# pcb_control_esp.net
KiCad netlist of a schematic drawn in EAGLE
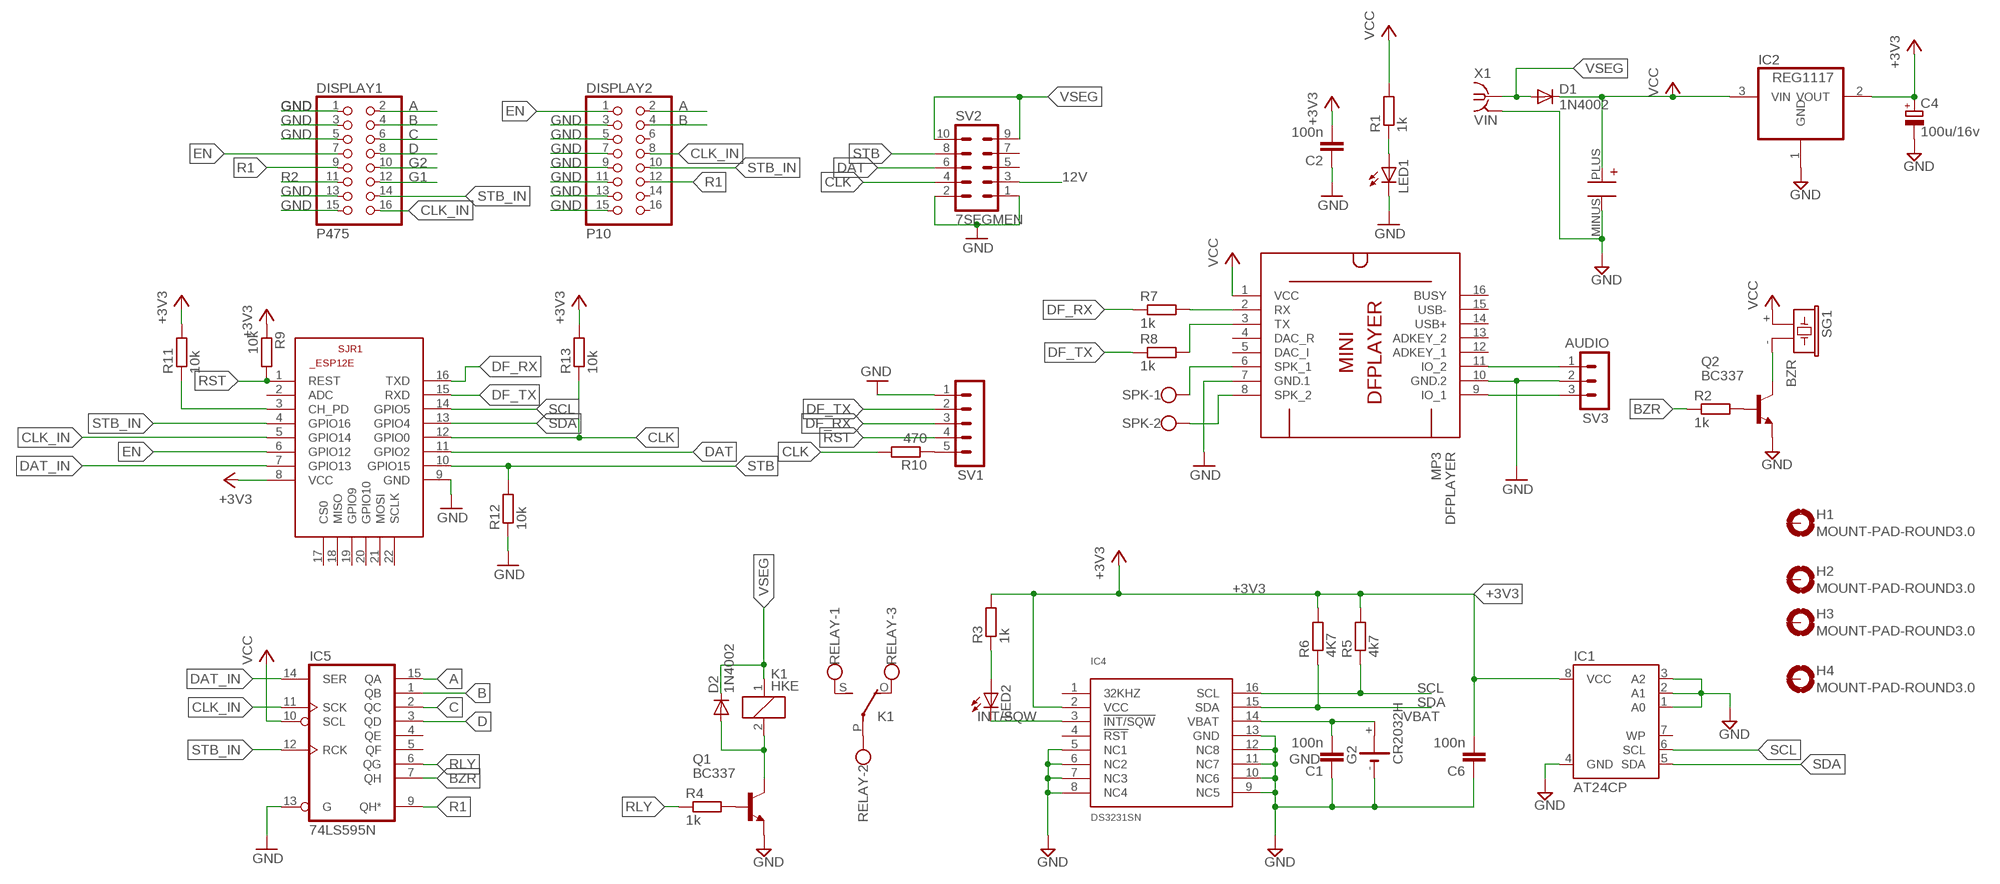
[diagram p0: schematic, sheet 1]

(export (version "E")
  (design (tool "Eeschema 10.0.6"))
  (components
    (comp (ref "C1")
      (value "100n")
      (footprint "eagle-import:C025-024X044")
      (libsource (lib "eagle-import") (part "C-EU025-024X044"))
    )
    (comp (ref "C2")
      (value "100n")
      (footprint "eagle-import:C025-024X044")
      (libsource (lib "eagle-import") (part "C-EU025-024X044"))
    )
    (comp (ref "C4")
      (value "100u/16v")
      (footprint "eagle-import:E2,5-5")
      (libsource (lib "eagle-import") (part "CPOL-EUE2.5-5"))
    )
    (comp (ref "C6")
      (value "100n")
      (footprint "eagle-import:C025-024X044")
      (libsource (lib "eagle-import") (part "C-EU025-024X044"))
    )
    (comp (ref "C24")
      (value "1000U")
      (footprint "eagle-import:EEU-FR1C471B")
      (libsource (lib "eagle-import") (part "EEU-FR1C471B"))
    )
    (comp (ref "D1")
      (value "1N4002")
      (footprint "eagle-import:DO35-10")
      (libsource (lib "eagle-import") (part "1N4148DO35-10"))
    )
    (comp (ref "D2")
      (value "1N4002")
      (footprint "eagle-import:DO35-10")
      (libsource (lib "eagle-import") (part "1N4148DO35-10"))
    )
    (comp (ref "DFPLAYER")
      (value "MP3")
      (footprint "eagle-import:DFPLAYER-MINI-MODULE")
      (libsource (lib "eagle-import") (part "DFPLAYER-MINI-MODULE"))
    )
    (comp (ref "DISPLAY1")
      (value "P475")
      (footprint "eagle-import:2X08")
      (libsource (lib "eagle-import") (part "PINHD-2X8"))
    )
    (comp (ref "DISPLAY2")
      (value "P10")
      (footprint "eagle-import:2X08")
      (libsource (lib "eagle-import") (part "PINHD-2X8"))
    )
    (comp (ref "G2")
      (value "CR2032H")
      (footprint "eagle-import:CR2032H")
      (libsource (lib "eagle-import") (part "CR2032H"))
    )
    (comp (ref "H1")
      (value "MOUNT-PAD-ROUND3.0")
      (footprint "eagle-import:3,0-PAD")
      (libsource (lib "eagle-import") (part "MOUNT-PAD-ROUND3.0"))
    )
    (comp (ref "H2")
      (value "MOUNT-PAD-ROUND3.0")
      (footprint "eagle-import:3,0-PAD")
      (libsource (lib "eagle-import") (part "MOUNT-PAD-ROUND3.0"))
    )
    (comp (ref "H3")
      (value "MOUNT-PAD-ROUND3.0")
      (footprint "eagle-import:3,0-PAD")
      (libsource (lib "eagle-import") (part "MOUNT-PAD-ROUND3.0"))
    )
    (comp (ref "H4")
      (value "MOUNT-PAD-ROUND3.0")
      (footprint "eagle-import:3,0-PAD")
      (libsource (lib "eagle-import") (part "MOUNT-PAD-ROUND3.0"))
    )
    (comp (ref "IC1")
      (value "AT24CP")
      (footprint "eagle-import:DIL08")
      (fields (field (name "MPN") "AT24C1024BW-SH-B"))
      (libsource (lib "eagle-import") (part "AT24CP"))
    )
    (comp (ref "IC2")
      (value "REG1117")
      (footprint "eagle-import:SOT223")
      (libsource (lib "eagle-import") (part "REG1117"))
    )
    (comp (ref "IC4")
      (value "DS3231SN")
      (footprint "eagle-import:SO16W")
      (libsource (lib "eagle-import") (part "DS3231SN"))
    )
    (comp (ref "IC5")
      (value "74LS595N")
      (footprint "eagle-import:DIL16")
      (libsource (lib "eagle-import") (part "74595NLS"))
    )
    (comp (ref "K1")
      (value "HKE")
      (footprint "eagle-import:ZF112")
      (libsource (lib "eagle-import") (part "ZF112"))
    )
    (comp (ref "LED1")
      (value "LED3MM")
      (footprint "eagle-import:LED3MM")
      (libsource (lib "eagle-import") (part "LED3MM"))
    )
    (comp (ref "LED2")
      (value "LED3MM")
      (footprint "eagle-import:LED3MM")
      (libsource (lib "eagle-import") (part "LED3MM"))
    )
    (comp (ref "Q1")
      (value "BC337")
      (footprint "eagle-import:TO92-EBC")
      (libsource (lib "eagle-import") (part "BC548"))
    )
    (comp (ref "Q2")
      (value "BC337")
      (footprint "eagle-import:TO92-EBC")
      (libsource (lib "eagle-import") (part "BC548"))
    )
    (comp (ref "R1")
      (value "1k")
      (footprint "eagle-import:0207_7")
      (libsource (lib "eagle-import") (part "R-EU_0207/7"))
    )
    (comp (ref "R2")
      (value "1k")
      (footprint "eagle-import:0207_7")
      (libsource (lib "eagle-import") (part "R-EU_0207/7"))
    )
    (comp (ref "R3")
      (value "1k")
      (footprint "eagle-import:0207_7")
      (libsource (lib "eagle-import") (part "R-EU_0207/7"))
    )
    (comp (ref "R4")
      (value "1k")
      (footprint "eagle-import:0207_7")
      (libsource (lib "eagle-import") (part "R-EU_0207/7"))
    )
    (comp (ref "R5")
      (value "4k7")
      (footprint "eagle-import:0207_7")
      (libsource (lib "eagle-import") (part "R-EU_0207/7"))
    )
    (comp (ref "R6")
      (value "4K7")
      (footprint "eagle-import:0207_7")
      (libsource (lib "eagle-import") (part "R-EU_0207/7"))
    )
    (comp (ref "R7")
      (value "1k")
      (footprint "eagle-import:0207_7")
      (libsource (lib "eagle-import") (part "R-EU_0207/7"))
    )
    (comp (ref "R8")
      (value "1k")
      (footprint "eagle-import:0207_7")
      (libsource (lib "eagle-import") (part "R-EU_0207/7"))
    )
    (comp (ref "R9")
      (value "10k")
      (footprint "eagle-import:0207_7")
      (libsource (lib "eagle-import") (part "R-EU_0207/7"))
    )
    (comp (ref "R10")
      (value "470")
      (footprint "eagle-import:0207_7")
      (libsource (lib "eagle-import") (part "R-EU_0207/7"))
    )
    (comp (ref "R11")
      (value "10k")
      (footprint "eagle-import:0207_7")
      (libsource (lib "eagle-import") (part "R-EU_0207/7"))
    )
    (comp (ref "R12")
      (value "10k")
      (footprint "eagle-import:0207_7")
      (libsource (lib "eagle-import") (part "R-EU_0207/7"))
    )
    (comp (ref "R13")
      (value "10k")
      (footprint "eagle-import:0207_7")
      (libsource (lib "eagle-import") (part "R-EU_0207/7"))
    )
    (comp (ref "RELAY")
      (value "W237-103")
      (footprint "eagle-import:W237-103")
      (fields (field (name "MPN") "237-103"))
      (libsource (lib "eagle-import") (part "W237-103"))
    )
    (comp (ref "SG1")
      (value "BZR")
      (footprint "eagle-import:F_CM12P")
      (libsource (lib "eagle-import") (part "F/CM12P"))
    )
    (comp (ref "SJR1")
      (value "ESP8266-12EESP12E")
      (footprint "eagle-import:ESP8266-ESP12E")
      (libsource (lib "eagle-import") (part "ESP8266-12EESP12E"))
    )
    (comp (ref "SPK")
      (value "W237-102")
      (footprint "eagle-import:W237-102")
      (fields (field (name "MPN") "237-102"))
      (libsource (lib "eagle-import") (part "W237-102"))
    )
    (comp (ref "SV1")
      (value "MA05-1")
      (footprint "eagle-import:MA05-1")
      (libsource (lib "eagle-import") (part "MA05-1"))
    )
    (comp (ref "SV2")
      (value "7SEGMEN")
      (footprint "eagle-import:MA05-2")
      (libsource (lib "eagle-import") (part "MA05-2"))
    )
    (comp (ref "SV3")
      (value "AUDIO")
      (footprint "eagle-import:MA03-1")
      (libsource (lib "eagle-import") (part "MA03-1"))
    )
    (comp (ref "X1")
      (value "VIN")
      (footprint "eagle-import:J502-ND")
      (libsource (lib "eagle-import") (part "SMA-J502-ND"))
    )
  )
  (nets
    (net (code "1") (name "+3V3") (class "Default")
      (node (ref "C2") (pin "2") (pinfunction "2_2") (pintype "passive"))
      (node (ref "C4") (pin "+") (pinfunction "+_+") (pintype "passive"))
      (node (ref "C6") (pin "2") (pinfunction "2_2") (pintype "passive"))
      (node (ref "IC1") (pin "8") (pinfunction "VCC_8") (pintype "power_in"))
      (node (ref "IC2") (pin "2") (pinfunction "VOUT_2") (pintype "output"))
      (node (ref "IC4") (pin "2") (pinfunction "VCC_2") (pintype "bidirectional"))
      (node (ref "R11") (pin "2") (pinfunction "2_2") (pintype "passive"))
      (node (ref "R13") (pin "2") (pinfunction "2_2") (pintype "passive"))
      (node (ref "R3") (pin "2") (pinfunction "2_2") (pintype "passive"))
      (node (ref "R5") (pin "2") (pinfunction "2_2") (pintype "passive"))
      (node (ref "R6") (pin "2") (pinfunction "2_2") (pintype "passive"))
      (node (ref "R9") (pin "1") (pinfunction "1_1") (pintype "passive"))
      (node (ref "SJR1") (pin "8") (pinfunction "VCC_8") (pintype "bidirectional"))
    )
    (net (code "2") (name "/12V") (class "Default")
      (node (ref "SV2") (pin "3") (pinfunction "3_3") (pintype "passive"))
    )
    (net (code "3") (name "/G1") (class "Default")
      (node (ref "DISPLAY1") (pin "12") (pinfunction "12_12") (pintype "passive"))
    )
    (net (code "4") (name "/G2") (class "Default")
      (node (ref "DISPLAY1") (pin "10") (pinfunction "10_10") (pintype "passive"))
    )
    (net (code "5") (name "/INT{slash}SQW") (class "Default")
      (node (ref "IC4") (pin "3") (pinfunction "~{INT/SQW}_3") (pintype "bidirectional"))
      (node (ref "LED2") (pin "K") (pinfunction "C_K") (pintype "passive"))
    )
    (net (code "6") (name "/R2") (class "Default")
      (node (ref "DISPLAY1") (pin "11") (pinfunction "11_11") (pintype "passive"))
    )
    (net (code "7") (name "/VBAT") (class "Default")
      (node (ref "C1") (pin "2") (pinfunction "2_2") (pintype "passive"))
      (node (ref "G2") (pin "+") (pinfunction "+_+") (pintype "passive"))
      (node (ref "IC4") (pin "14") (pinfunction "VBAT_14") (pintype "bidirectional"))
    )
    (net (code "8") (name "A") (class "Default")
      (node (ref "DISPLAY1") (pin "2") (pinfunction "2_2") (pintype "passive"))
      (node (ref "DISPLAY2") (pin "2") (pinfunction "2_2") (pintype "passive"))
      (node (ref "IC5") (pin "15") (pinfunction "QA_15") (pintype "tri_state"))
    )
    (net (code "9") (name "B") (class "Default")
      (node (ref "DISPLAY1") (pin "4") (pinfunction "4_4") (pintype "passive"))
      (node (ref "DISPLAY2") (pin "4") (pinfunction "4_4") (pintype "passive"))
      (node (ref "IC5") (pin "1") (pinfunction "QB_1") (pintype "tri_state"))
    )
    (net (code "10") (name "BZR") (class "Default")
      (node (ref "IC5") (pin "7") (pinfunction "QH_7") (pintype "tri_state"))
      (node (ref "R2") (pin "1") (pinfunction "1_1") (pintype "passive"))
    )
    (net (code "11") (name "C") (class "Default")
      (node (ref "DISPLAY1") (pin "6") (pinfunction "6_6") (pintype "passive"))
      (node (ref "IC5") (pin "2") (pinfunction "QC_2") (pintype "tri_state"))
    )
    (net (code "12") (name "CLK") (class "Default")
      (node (ref "R10") (pin "2") (pinfunction "2_2") (pintype "passive"))
      (node (ref "R13") (pin "1") (pinfunction "1_1") (pintype "passive"))
      (node (ref "SJR1") (pin "12") (pinfunction "GPIO0_12") (pintype "bidirectional"))
      (node (ref "SV2") (pin "4") (pinfunction "4_4") (pintype "passive"))
    )
    (net (code "13") (name "CLK_IN") (class "Default")
      (node (ref "DISPLAY1") (pin "16") (pinfunction "16_16") (pintype "passive"))
      (node (ref "DISPLAY2") (pin "8") (pinfunction "8_8") (pintype "passive"))
      (node (ref "IC5") (pin "11") (pinfunction "SCK_11") (pintype "input"))
      (node (ref "SJR1") (pin "5") (pinfunction "GPIO14_5") (pintype "bidirectional"))
    )
    (net (code "14") (name "D") (class "Default")
      (node (ref "DISPLAY1") (pin "8") (pinfunction "8_8") (pintype "passive"))
      (node (ref "IC5") (pin "3") (pinfunction "QD_3") (pintype "tri_state"))
    )
    (net (code "15") (name "DAT") (class "Default")
      (node (ref "SJR1") (pin "11") (pinfunction "GPIO2_11") (pintype "bidirectional"))
      (node (ref "SV2") (pin "6") (pinfunction "6_6") (pintype "passive"))
    )
    (net (code "16") (name "DAT_IN") (class "Default")
      (node (ref "IC5") (pin "14") (pinfunction "SER_14") (pintype "input"))
      (node (ref "SJR1") (pin "7") (pinfunction "GPIO13_7") (pintype "bidirectional"))
    )
    (net (code "17") (name "DF_RX") (class "Default")
      (node (ref "R7") (pin "1") (pinfunction "1_1") (pintype "passive"))
      (node (ref "SJR1") (pin "16") (pinfunction "TXD_16") (pintype "bidirectional"))
      (node (ref "SV1") (pin "3") (pinfunction "3_3") (pintype "passive"))
    )
    (net (code "18") (name "DF_TX") (class "Default")
      (node (ref "R8") (pin "1") (pinfunction "1_1") (pintype "passive"))
      (node (ref "SJR1") (pin "15") (pinfunction "RXD_15") (pintype "bidirectional"))
      (node (ref "SV1") (pin "2") (pinfunction "2_2") (pintype "passive"))
    )
    (net (code "19") (name "EN") (class "Default")
      (node (ref "DISPLAY1") (pin "7") (pinfunction "7_7") (pintype "passive"))
      (node (ref "DISPLAY2") (pin "1") (pinfunction "1_1") (pintype "passive"))
      (node (ref "SJR1") (pin "6") (pinfunction "GPIO12_6") (pintype "bidirectional"))
    )
    (net (code "20") (name "GND") (class "Default")
      (node (ref "C1") (pin "1") (pinfunction "1_1") (pintype "passive"))
      (node (ref "C2") (pin "1") (pinfunction "1_1") (pintype "passive"))
      (node (ref "C24") (pin "MINUS") (pinfunction "MINUS_MINUS") (pintype "bidirectional"))
      (node (ref "C4") (pin "-") (pinfunction "-_-") (pintype "passive"))
      (node (ref "C6") (pin "1") (pinfunction "1_1") (pintype "passive"))
      (node (ref "DFPLAYER") (pin "10") (pinfunction "GND.2_10") (pintype "power_in"))
      (node (ref "DFPLAYER") (pin "7") (pinfunction "GND.1_7") (pintype "power_in"))
      (node (ref "DISPLAY1") (pin "1") (pinfunction "1_1") (pintype "passive"))
      (node (ref "DISPLAY1") (pin "13") (pinfunction "13_13") (pintype "passive"))
      (node (ref "DISPLAY1") (pin "15") (pinfunction "15_15") (pintype "passive"))
      (node (ref "DISPLAY1") (pin "3") (pinfunction "3_3") (pintype "passive"))
      (node (ref "DISPLAY1") (pin "5") (pinfunction "5_5") (pintype "passive"))
      (node (ref "DISPLAY2") (pin "11") (pinfunction "11_11") (pintype "passive"))
      (node (ref "DISPLAY2") (pin "13") (pinfunction "13_13") (pintype "passive"))
      (node (ref "DISPLAY2") (pin "15") (pinfunction "15_15") (pintype "passive"))
      (node (ref "DISPLAY2") (pin "3") (pinfunction "3_3") (pintype "passive"))
      (node (ref "DISPLAY2") (pin "5") (pinfunction "5_5") (pintype "passive"))
      (node (ref "DISPLAY2") (pin "7") (pinfunction "7_7") (pintype "passive"))
      (node (ref "DISPLAY2") (pin "9") (pinfunction "9_9") (pintype "passive"))
      (node (ref "G2") (pin "-") (pinfunction "-_-") (pintype "passive"))
      (node (ref "IC1") (pin "1") (pinfunction "A0_1") (pintype "input"))
      (node (ref "IC1") (pin "2") (pinfunction "A1_2") (pintype "input"))
      (node (ref "IC1") (pin "3") (pinfunction "A2_3") (pintype "input"))
      (node (ref "IC1") (pin "4") (pinfunction "GND_4") (pintype "power_in"))
      (node (ref "IC2") (pin "1") (pinfunction "GND_1") (pintype "power_in"))
      (node (ref "IC4") (pin "10") (pinfunction "NC6_10") (pintype "bidirectional"))
      (node (ref "IC4") (pin "11") (pinfunction "NC7_11") (pintype "bidirectional"))
      (node (ref "IC4") (pin "12") (pinfunction "NC8_12") (pintype "bidirectional"))
      (node (ref "IC4") (pin "13") (pinfunction "GND_13") (pintype "bidirectional"))
      (node (ref "IC4") (pin "5") (pinfunction "NC1_5") (pintype "bidirectional"))
      (node (ref "IC4") (pin "6") (pinfunction "NC2_6") (pintype "bidirectional"))
      (node (ref "IC4") (pin "7") (pinfunction "NC3_7") (pintype "bidirectional"))
      (node (ref "IC4") (pin "8") (pinfunction "NC4_8") (pintype "bidirectional"))
      (node (ref "IC4") (pin "9") (pinfunction "NC5_9") (pintype "bidirectional"))
      (node (ref "IC5") (pin "13") (pinfunction "G_13") (pintype "input"))
      (node (ref "LED1") (pin "K") (pinfunction "C_K") (pintype "passive"))
      (node (ref "Q1") (pin "E") (pinfunction "E_E") (pintype "passive"))
      (node (ref "Q2") (pin "E") (pinfunction "E_E") (pintype "passive"))
      (node (ref "R12") (pin "1") (pinfunction "1_1") (pintype "passive"))
      (node (ref "SJR1") (pin "9") (pinfunction "GND_9") (pintype "bidirectional"))
      (node (ref "SV1") (pin "1") (pinfunction "1_1") (pintype "passive"))
      (node (ref "SV2") (pin "1") (pinfunction "1_1") (pintype "passive"))
      (node (ref "SV2") (pin "2") (pinfunction "2_2") (pintype "passive"))
      (node (ref "SV3") (pin "2") (pinfunction "2_2") (pintype "passive"))
      (node (ref "X1") (pin "2") (pinfunction "2_2") (pintype "passive"))
      (node (ref "X1") (pin "5") (pinfunction "2_5") (pintype "passive"))
    )
    (net (code "21") (name "Net-(D2-PadA)") (class "Default")
      (node (ref "D2") (pin "A") (pinfunction "A_A") (pintype "passive"))
      (node (ref "K1") (pin "2") (pinfunction "2_2") (pintype "passive"))
      (node (ref "Q1") (pin "C") (pinfunction "C_C") (pintype "passive"))
    )
    (net (code "22") (name "Net-(DFPLAYER-IO_1)") (class "Default")
      (node (ref "DFPLAYER") (pin "9") (pinfunction "IO_1_9") (pintype "bidirectional"))
      (node (ref "SV3") (pin "3") (pinfunction "3_3") (pintype "passive"))
    )
    (net (code "23") (name "Net-(DFPLAYER-IO_2)") (class "Default")
      (node (ref "DFPLAYER") (pin "11") (pinfunction "IO_2_11") (pintype "bidirectional"))
      (node (ref "SV3") (pin "1") (pinfunction "1_1") (pintype "passive"))
    )
    (net (code "24") (name "Net-(DFPLAYER-RX)") (class "Default")
      (node (ref "DFPLAYER") (pin "2") (pinfunction "RX_2") (pintype "bidirectional"))
      (node (ref "R7") (pin "2") (pinfunction "2_2") (pintype "passive"))
    )
    (net (code "25") (name "Net-(DFPLAYER-SPK_1)") (class "Default")
      (node (ref "DFPLAYER") (pin "6") (pinfunction "SPK_1_6") (pintype "bidirectional"))
      (node (ref "SPK") (pin "1") (pinfunction "KL_1") (pintype "passive"))
    )
    (net (code "26") (name "Net-(DFPLAYER-SPK_2)") (class "Default")
      (node (ref "DFPLAYER") (pin "8") (pinfunction "SPK_2_8") (pintype "bidirectional"))
      (node (ref "SPK") (pin "2") (pinfunction "KL_2") (pintype "passive"))
    )
    (net (code "27") (name "Net-(DFPLAYER-TX)") (class "Default")
      (node (ref "DFPLAYER") (pin "3") (pinfunction "TX_3") (pintype "bidirectional"))
      (node (ref "R8") (pin "2") (pinfunction "2_2") (pintype "passive"))
    )
    (net (code "28") (name "Net-(LED1-PadA)") (class "Default")
      (node (ref "LED1") (pin "A") (pinfunction "A_A") (pintype "passive"))
      (node (ref "R1") (pin "1") (pinfunction "1_1") (pintype "passive"))
    )
    (net (code "29") (name "Net-(LED2-PadA)") (class "Default")
      (node (ref "LED2") (pin "A") (pinfunction "A_A") (pintype "passive"))
      (node (ref "R3") (pin "1") (pinfunction "1_1") (pintype "passive"))
    )
    (net (code "30") (name "Net-(Q1-PadB)") (class "Default")
      (node (ref "Q1") (pin "B") (pinfunction "B_B") (pintype "passive"))
      (node (ref "R4") (pin "2") (pinfunction "2_2") (pintype "passive"))
    )
    (net (code "31") (name "Net-(Q2-PadB)") (class "Default")
      (node (ref "Q2") (pin "B") (pinfunction "B_B") (pintype "passive"))
      (node (ref "R2") (pin "2") (pinfunction "2_2") (pintype "passive"))
    )
    (net (code "32") (name "Net-(R10-Pad1)") (class "Default")
      (node (ref "R10") (pin "1") (pinfunction "1_1") (pintype "passive"))
      (node (ref "SV1") (pin "5") (pinfunction "5_5") (pintype "passive"))
    )
    (net (code "33") (name "Net-(RELAYA-KL)") (class "Default")
      (node (ref "K1") (pin "S") (pinfunction "S_S") (pintype "passive"))
      (node (ref "RELAY") (pin "1") (pinfunction "KL_1") (pintype "passive"))
    )
    (net (code "34") (name "Net-(RELAYB-KL)") (class "Default")
      (node (ref "K1") (pin "P") (pinfunction "P_P") (pintype "passive"))
      (node (ref "RELAY") (pin "2") (pinfunction "KL_2") (pintype "passive"))
    )
    (net (code "35") (name "Net-(RELAYC-KL)") (class "Default")
      (node (ref "K1") (pin "O") (pinfunction "O_O") (pintype "passive"))
      (node (ref "RELAY") (pin "3") (pinfunction "KL_3") (pintype "passive"))
    )
    (net (code "36") (name "Net-(SG1-2)") (class "Default")
      (node (ref "Q2") (pin "C") (pinfunction "C_C") (pintype "passive"))
      (node (ref "SG1") (pin "-") (pinfunction "2_-") (pintype "passive"))
    )
    (net (code "37") (name "Net-(SJR1-CH_PD)") (class "Default")
      (node (ref "R11") (pin "1") (pinfunction "1_1") (pintype "passive"))
      (node (ref "SJR1") (pin "3") (pinfunction "CH_PD_3") (pintype "bidirectional"))
    )
    (net (code "38") (name "R1") (class "Default")
      (node (ref "DISPLAY1") (pin "9") (pinfunction "9_9") (pintype "passive"))
      (node (ref "DISPLAY2") (pin "12") (pinfunction "12_12") (pintype "passive"))
      (node (ref "IC5") (pin "9") (pinfunction "QH*_9") (pintype "tri_state"))
    )
    (net (code "39") (name "RLY") (class "Default")
      (node (ref "IC5") (pin "6") (pinfunction "QG_6") (pintype "tri_state"))
      (node (ref "R4") (pin "1") (pinfunction "1_1") (pintype "passive"))
    )
    (net (code "40") (name "RST") (class "Default")
      (node (ref "R9") (pin "2") (pinfunction "2_2") (pintype "passive"))
      (node (ref "SJR1") (pin "1") (pinfunction "REST_1") (pintype "bidirectional"))
      (node (ref "SV1") (pin "4") (pinfunction "4_4") (pintype "passive"))
    )
    (net (code "41") (name "SCL") (class "Default")
      (node (ref "IC1") (pin "6") (pinfunction "SCL_6") (pintype "bidirectional"))
      (node (ref "IC4") (pin "16") (pinfunction "SCL_16") (pintype "bidirectional"))
      (node (ref "R5") (pin "1") (pinfunction "1_1") (pintype "passive"))
      (node (ref "SJR1") (pin "14") (pinfunction "GPIO5_14") (pintype "bidirectional"))
    )
    (net (code "42") (name "SDA") (class "Default")
      (node (ref "IC1") (pin "5") (pinfunction "SDA_5") (pintype "bidirectional"))
      (node (ref "IC4") (pin "15") (pinfunction "SDA_15") (pintype "bidirectional"))
      (node (ref "R6") (pin "1") (pinfunction "1_1") (pintype "passive"))
      (node (ref "SJR1") (pin "13") (pinfunction "GPIO4_13") (pintype "bidirectional"))
    )
    (net (code "43") (name "STB") (class "Default")
      (node (ref "R12") (pin "2") (pinfunction "2_2") (pintype "passive"))
      (node (ref "SJR1") (pin "10") (pinfunction "GPIO15_10") (pintype "bidirectional"))
      (node (ref "SV2") (pin "8") (pinfunction "8_8") (pintype "passive"))
    )
    (net (code "44") (name "STB_IN") (class "Default")
      (node (ref "DISPLAY1") (pin "14") (pinfunction "14_14") (pintype "passive"))
      (node (ref "DISPLAY2") (pin "10") (pinfunction "10_10") (pintype "passive"))
      (node (ref "IC5") (pin "12") (pinfunction "RCK_12") (pintype "input"))
      (node (ref "SJR1") (pin "4") (pinfunction "GPIO16_4") (pintype "bidirectional"))
    )
    (net (code "45") (name "VCC") (class "Default")
      (node (ref "C24") (pin "PLUS") (pinfunction "PLUS_PLUS") (pintype "bidirectional"))
      (node (ref "D1") (pin "C") (pinfunction "C_C") (pintype "passive"))
      (node (ref "DFPLAYER") (pin "1") (pinfunction "VCC_1") (pintype "power_in"))
      (node (ref "IC2") (pin "3") (pinfunction "VIN_3") (pintype "input"))
      (node (ref "IC5") (pin "10") (pinfunction "SCL_10") (pintype "input"))
      (node (ref "R1") (pin "2") (pinfunction "2_2") (pintype "passive"))
      (node (ref "SG1") (pin "+") (pinfunction "1_+") (pintype "passive"))
    )
    (net (code "46") (name "VSEG") (class "Default")
      (node (ref "D1") (pin "A") (pinfunction "A_A") (pintype "passive"))
      (node (ref "D2") (pin "C") (pinfunction "C_C") (pintype "passive"))
      (node (ref "K1") (pin "1") (pinfunction "1_1") (pintype "passive"))
      (node (ref "SV2") (pin "10") (pinfunction "10_10") (pintype "passive"))
      (node (ref "SV2") (pin "9") (pinfunction "9_9") (pintype "passive"))
      (node (ref "X1") (pin "3") (pinfunction "1_3") (pintype "passive"))
      (node (ref "X1") (pin "4") (pinfunction "1_4") (pintype "passive"))
    )
    (net (code "47") (name "unconnected-(DFPLAYER-ADKEY_1-Pad12)") (class "Default")
      (node (ref "DFPLAYER") (pin "12") (pinfunction "ADKEY_1_12") (pintype "bidirectional"))
    )
    (net (code "48") (name "unconnected-(DFPLAYER-ADKEY_2-Pad13)") (class "Default")
      (node (ref "DFPLAYER") (pin "13") (pinfunction "ADKEY_2_13") (pintype "bidirectional"))
    )
    (net (code "49") (name "unconnected-(DFPLAYER-BUSY-Pad16)") (class "Default")
      (node (ref "DFPLAYER") (pin "16") (pinfunction "BUSY_16") (pintype "bidirectional"))
    )
    (net (code "50") (name "unconnected-(DFPLAYER-DAC_I-Pad5)") (class "Default")
      (node (ref "DFPLAYER") (pin "5") (pinfunction "DAC_I_5") (pintype "bidirectional"))
    )
    (net (code "51") (name "unconnected-(DFPLAYER-DAC_R-Pad4)") (class "Default")
      (node (ref "DFPLAYER") (pin "4") (pinfunction "DAC_R_4") (pintype "bidirectional"))
    )
    (net (code "52") (name "unconnected-(DFPLAYER-USB+-Pad14)") (class "Default")
      (node (ref "DFPLAYER") (pin "14") (pinfunction "USB+_14") (pintype "bidirectional"))
    )
    (net (code "53") (name "unconnected-(DFPLAYER-USB--Pad15)") (class "Default")
      (node (ref "DFPLAYER") (pin "15") (pinfunction "USB-_15") (pintype "bidirectional"))
    )
    (net (code "54") (name "unconnected-(DISPLAY2-Pad6)") (class "Default")
      (node (ref "DISPLAY2") (pin "6") (pinfunction "6_6") (pintype "passive"))
    )
    (net (code "55") (name "unconnected-(DISPLAY2-Pad14)") (class "Default")
      (node (ref "DISPLAY2") (pin "14") (pinfunction "14_14") (pintype "passive"))
    )
    (net (code "56") (name "unconnected-(DISPLAY2-Pad16)") (class "Default")
      (node (ref "DISPLAY2") (pin "16") (pinfunction "16_16") (pintype "passive"))
    )
    (net (code "57") (name "unconnected-(H1-MOUNT-PadB3,0)") (class "Default")
      (node (ref "H1") (pin "B3,0") (pinfunction "MOUNT_B3,0") (pintype "passive"))
    )
    (net (code "58") (name "unconnected-(H2-MOUNT-PadB3,0)") (class "Default")
      (node (ref "H2") (pin "B3,0") (pinfunction "MOUNT_B3,0") (pintype "passive"))
    )
    (net (code "59") (name "unconnected-(H3-MOUNT-PadB3,0)") (class "Default")
      (node (ref "H3") (pin "B3,0") (pinfunction "MOUNT_B3,0") (pintype "passive"))
    )
    (net (code "60") (name "unconnected-(H4-MOUNT-PadB3,0)") (class "Default")
      (node (ref "H4") (pin "B3,0") (pinfunction "MOUNT_B3,0") (pintype "passive"))
    )
    (net (code "61") (name "unconnected-(IC1-WP-Pad7)") (class "Default")
      (node (ref "IC1") (pin "7") (pinfunction "WP_7") (pintype "input"))
    )
    (net (code "62") (name "unconnected-(IC4-32KHZ-Pad1)") (class "Default")
      (node (ref "IC4") (pin "1") (pinfunction "32KHZ_1") (pintype "bidirectional"))
    )
    (net (code "63") (name "unconnected-(IC4-~{RST}-Pad4)") (class "Default")
      (node (ref "IC4") (pin "4") (pinfunction "~{RST}_4") (pintype "bidirectional"))
    )
    (net (code "64") (name "unconnected-(IC5A-QE-Pad4)") (class "Default")
      (node (ref "IC5") (pin "4") (pinfunction "QE_4") (pintype "tri_state"))
    )
    (net (code "65") (name "unconnected-(IC5A-QF-Pad5)") (class "Default")
      (node (ref "IC5") (pin "5") (pinfunction "QF_5") (pintype "tri_state"))
    )
    (net (code "66") (name "unconnected-(SJR1-ADC-Pad2)") (class "Default")
      (node (ref "SJR1") (pin "2") (pinfunction "ADC_2") (pintype "bidirectional"))
    )
    (net (code "67") (name "unconnected-(SJR1-CS0-Pad17)") (class "Default")
      (node (ref "SJR1") (pin "17") (pinfunction "CS0_17") (pintype "bidirectional"))
    )
    (net (code "68") (name "unconnected-(SJR1-GPIO9-Pad19)") (class "Default")
      (node (ref "SJR1") (pin "19") (pinfunction "GPIO9_19") (pintype "bidirectional"))
    )
    (net (code "69") (name "unconnected-(SJR1-GPIO10-Pad20)") (class "Default")
      (node (ref "SJR1") (pin "20") (pinfunction "GPIO10_20") (pintype "bidirectional"))
    )
    (net (code "70") (name "unconnected-(SJR1-MISO-Pad18)") (class "Default")
      (node (ref "SJR1") (pin "18") (pinfunction "MISO_18") (pintype "bidirectional"))
    )
    (net (code "71") (name "unconnected-(SJR1-MOSI-Pad21)") (class "Default")
      (node (ref "SJR1") (pin "21") (pinfunction "MOSI_21") (pintype "bidirectional"))
    )
    (net (code "72") (name "unconnected-(SJR1-SCLK-Pad22)") (class "Default")
      (node (ref "SJR1") (pin "22") (pinfunction "SCLK_22") (pintype "bidirectional"))
    )
    (net (code "73") (name "unconnected-(SV2-Pad5)") (class "Default")
      (node (ref "SV2") (pin "5") (pinfunction "5_5") (pintype "passive"))
    )
    (net (code "74") (name "unconnected-(SV2-Pad7)") (class "Default")
      (node (ref "SV2") (pin "7") (pinfunction "7_7") (pintype "passive"))
    )
  )
)
